# STM32.net
KiCad netlist of a schematic drawn in Altium Designer
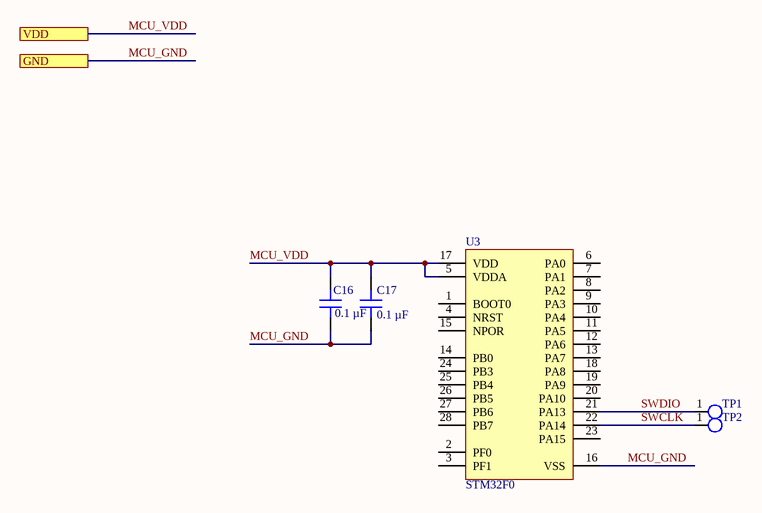
[diagram p0: STM32.SchDoc]

(export (version "E")
  (design (tool "Eeschema 10.0.6"))
  (components
    (comp (ref "C16")
      (value "0.1 µF")
      (footprint "CAP 0402_1005")
      (description "CAP CER 0.1UF 16V X7R 0402")
      (fields (field (name "PART NUMBER") "C0402C104K4RACAUTO") (field (name "MANUFACTURER") "KEMET"))
      (libsource (lib "Celestial Altium Library - altium_library") (part "Capacitor"))
    )
    (comp (ref "C17")
      (value "0.1 µF")
      (footprint "CAP 0402_1005")
      (description "CAP CER 0.1UF 16V X7R 0402")
      (fields (field (name "PART NUMBER") "C0402C104K4RACAUTO") (field (name "MANUFACTURER") "KEMET"))
      (libsource (lib "Celestial Altium Library - altium_library") (part "Capacitor"))
    )
    (comp (ref "TP1")
      (value "0.635mm")
      (footprint "TP  0.635mm")
      (description "Test point")
      (libsource (lib "IC") (part "TP 0.635mm"))
    )
    (comp (ref "TP2")
      (value "0.635mm")
      (footprint "TP  0.635mm")
      (description "Test point")
      (libsource (lib "IC") (part "TP 0.635mm"))
    )
    (comp (ref "U3")
      (value "STM32F0")
      (footprint "QFN50P400X400X60-28N")
      (description "6-DOF IMU")
      (libsource (lib "IC") (part "STM32F0"))
    )
  )
  (nets
    (net (code "1") (name "/MCU_GND") (class "Default")
      (node (ref "C16") (pin "1") (pinfunction "1_1") (pintype "passive"))
      (node (ref "C17") (pin "1") (pinfunction "1_1") (pintype "passive"))
      (node (ref "U3") (pin "16") (pinfunction "VSS_16") (pintype "passive"))
    )
    (net (code "2") (name "/MCU_VDD") (class "Default")
      (node (ref "C16") (pin "2") (pinfunction "2_2") (pintype "passive"))
      (node (ref "C17") (pin "2") (pinfunction "2_2") (pintype "passive"))
      (node (ref "U3") (pin "17") (pinfunction "VDD_17") (pintype "passive"))
      (node (ref "U3") (pin "5") (pinfunction "VDDA_5") (pintype "passive"))
    )
    (net (code "3") (name "/SWCLK") (class "Default")
      (node (ref "TP2") (pin "1") (pinfunction "TP_1") (pintype "passive"))
      (node (ref "U3") (pin "22") (pinfunction "PA14_22") (pintype "passive"))
    )
    (net (code "4") (name "/SWDIO") (class "Default")
      (node (ref "TP1") (pin "1") (pinfunction "TP_1") (pintype "passive"))
      (node (ref "U3") (pin "21") (pinfunction "PA13_21") (pintype "passive"))
    )
    (net (code "5") (name "unconnected-(U3-BOOT0-Pad1)") (class "Default")
      (node (ref "U3") (pin "1") (pinfunction "BOOT0_1") (pintype "passive"))
    )
    (net (code "6") (name "unconnected-(U3-NPOR-Pad15)") (class "Default")
      (node (ref "U3") (pin "15") (pinfunction "NPOR_15") (pintype "passive"))
    )
    (net (code "7") (name "unconnected-(U3-NRST-Pad4)") (class "Default")
      (node (ref "U3") (pin "4") (pinfunction "NRST_4") (pintype "passive"))
    )
    (net (code "8") (name "unconnected-(U3-PA0-Pad6)") (class "Default")
      (node (ref "U3") (pin "6") (pinfunction "PA0_6") (pintype "passive"))
    )
    (net (code "9") (name "unconnected-(U3-PA1-Pad7)") (class "Default")
      (node (ref "U3") (pin "7") (pinfunction "PA1_7") (pintype "passive"))
    )
    (net (code "10") (name "unconnected-(U3-PA2-Pad8)") (class "Default")
      (node (ref "U3") (pin "8") (pinfunction "PA2_8") (pintype "passive"))
    )
    (net (code "11") (name "unconnected-(U3-PA3-Pad9)") (class "Default")
      (node (ref "U3") (pin "9") (pinfunction "PA3_9") (pintype "passive"))
    )
    (net (code "12") (name "unconnected-(U3-PA4-Pad10)") (class "Default")
      (node (ref "U3") (pin "10") (pinfunction "PA4_10") (pintype "passive"))
    )
    (net (code "13") (name "unconnected-(U3-PA5-Pad11)") (class "Default")
      (node (ref "U3") (pin "11") (pinfunction "PA5_11") (pintype "passive"))
    )
    (net (code "14") (name "unconnected-(U3-PA6-Pad12)") (class "Default")
      (node (ref "U3") (pin "12") (pinfunction "PA6_12") (pintype "passive"))
    )
    (net (code "15") (name "unconnected-(U3-PA7-Pad13)") (class "Default")
      (node (ref "U3") (pin "13") (pinfunction "PA7_13") (pintype "passive"))
    )
    (net (code "16") (name "unconnected-(U3-PA8-Pad18)") (class "Default")
      (node (ref "U3") (pin "18") (pinfunction "PA8_18") (pintype "passive"))
    )
    (net (code "17") (name "unconnected-(U3-PA9-Pad19)") (class "Default")
      (node (ref "U3") (pin "19") (pinfunction "PA9_19") (pintype "passive"))
    )
    (net (code "18") (name "unconnected-(U3-PA10-Pad20)") (class "Default")
      (node (ref "U3") (pin "20") (pinfunction "PA10_20") (pintype "passive"))
    )
    (net (code "19") (name "unconnected-(U3-PA15-Pad23)") (class "Default")
      (node (ref "U3") (pin "23") (pinfunction "PA15_23") (pintype "passive"))
    )
    (net (code "20") (name "unconnected-(U3-PB0-Pad14)") (class "Default")
      (node (ref "U3") (pin "14") (pinfunction "PB0_14") (pintype "passive"))
    )
    (net (code "21") (name "unconnected-(U3-PB3-Pad24)") (class "Default")
      (node (ref "U3") (pin "24") (pinfunction "PB3_24") (pintype "passive"))
    )
    (net (code "22") (name "unconnected-(U3-PB4-Pad25)") (class "Default")
      (node (ref "U3") (pin "25") (pinfunction "PB4_25") (pintype "passive"))
    )
    (net (code "23") (name "unconnected-(U3-PB5-Pad26)") (class "Default")
      (node (ref "U3") (pin "26") (pinfunction "PB5_26") (pintype "passive"))
    )
    (net (code "24") (name "unconnected-(U3-PB6-Pad27)") (class "Default")
      (node (ref "U3") (pin "27") (pinfunction "PB6_27") (pintype "passive"))
    )
    (net (code "25") (name "unconnected-(U3-PB7-Pad28)") (class "Default")
      (node (ref "U3") (pin "28") (pinfunction "PB7_28") (pintype "passive"))
    )
    (net (code "26") (name "unconnected-(U3-PF0-Pad2)") (class "Default")
      (node (ref "U3") (pin "2") (pinfunction "PF0_2") (pintype "passive"))
    )
    (net (code "27") (name "unconnected-(U3-PF1-Pad3)") (class "Default")
      (node (ref "U3") (pin "3") (pinfunction "PF1_3") (pintype "passive"))
    )
  )
)
